# dual_encoder_shield_3v.net
KiCad netlist of a schematic drawn in EAGLE
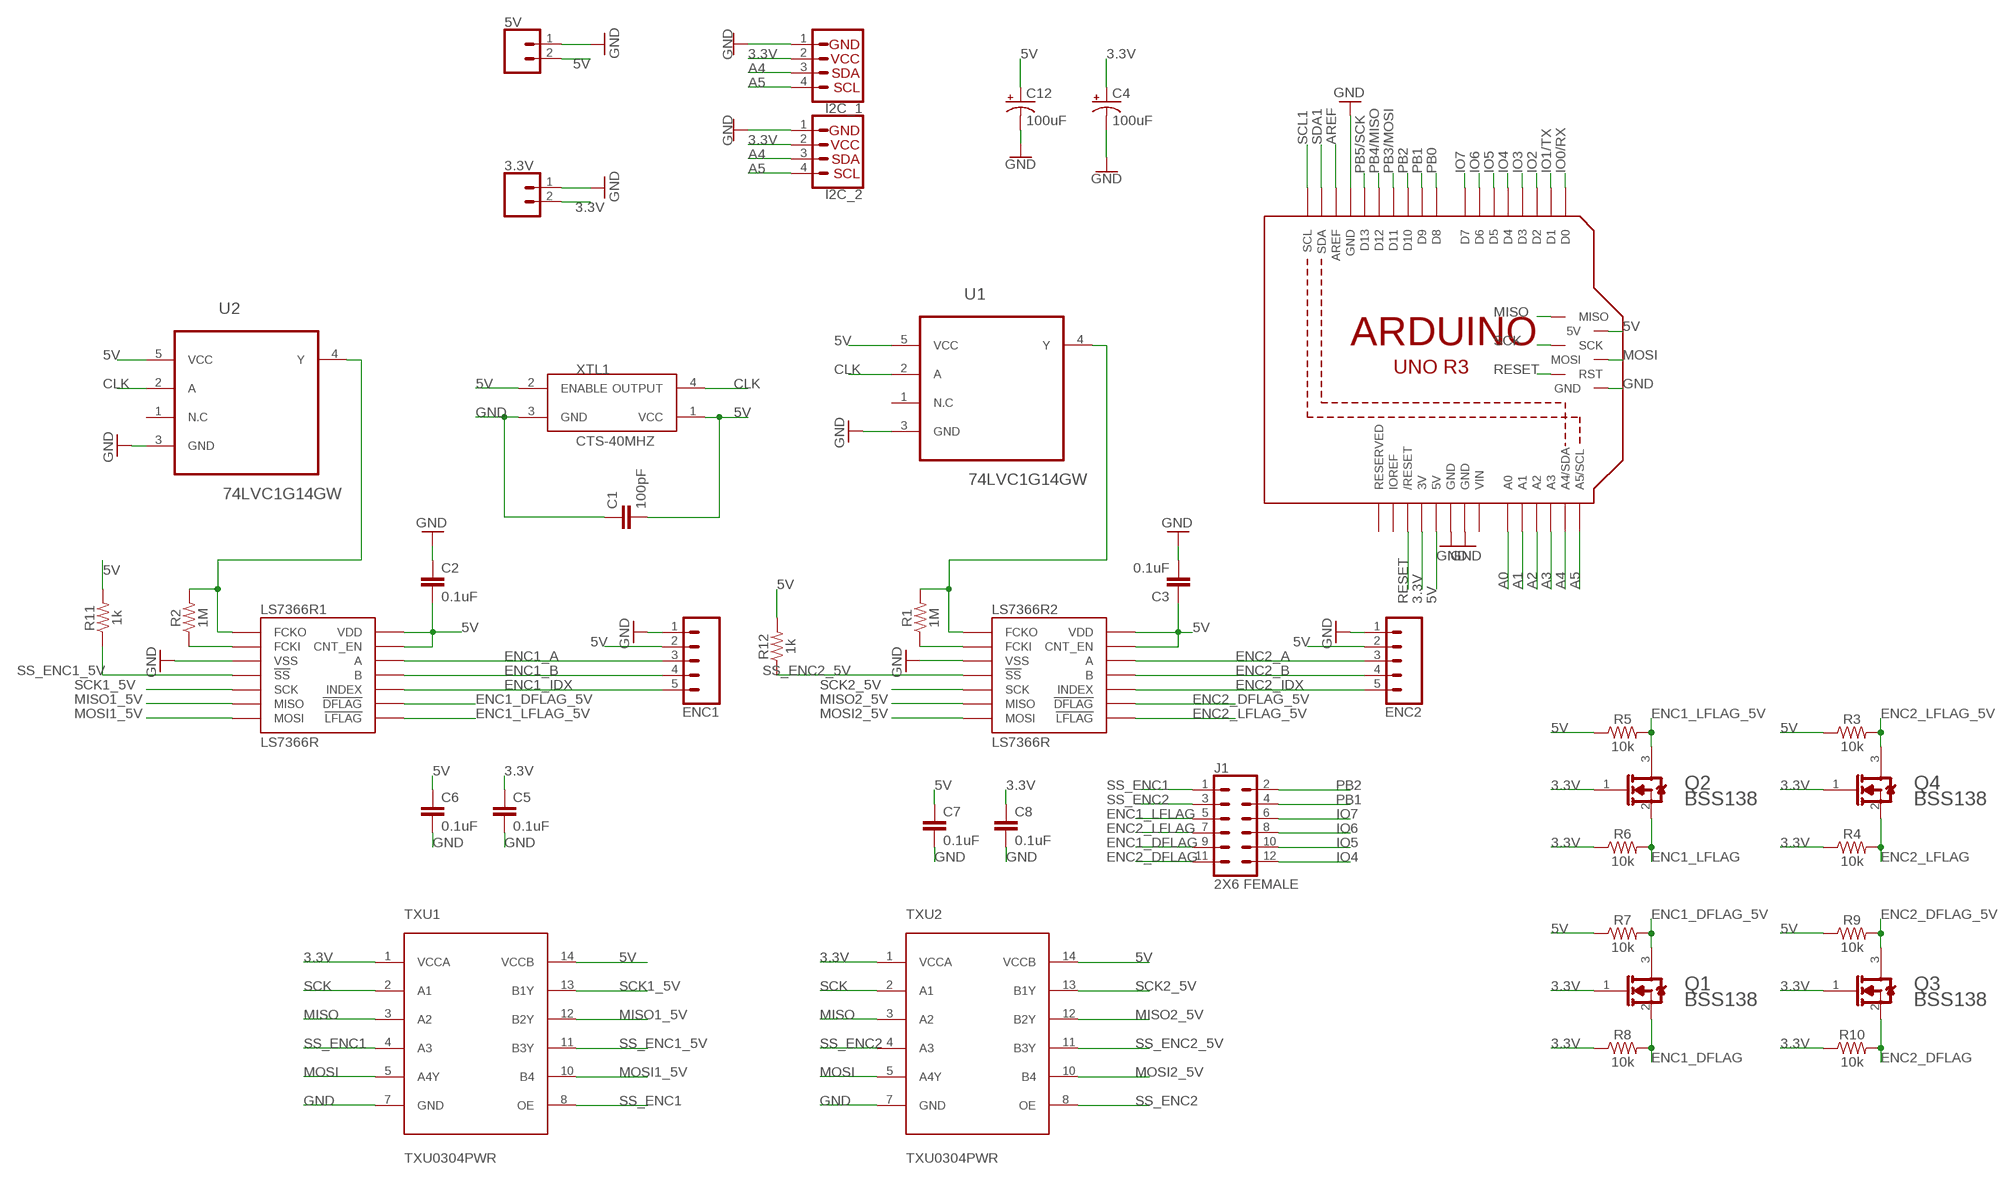
[diagram p0: schematic, sheet 1]

(export (version "E")
  (design (tool "Eeschema 10.0.6"))
  (components
    (comp (ref "3.3V")
      (value "CONN_02-JST-2MM-SMT")
      (footprint "eagle-import:JST-2-SMD")
      (libsource (lib "eagle-import") (part "CONN_02-JST-2MM-SMT"))
    )
    (comp (ref "5V")
      (value "CONN_02-JST-2MM-SMT")
      (footprint "eagle-import:JST-2-SMD")
      (libsource (lib "eagle-import") (part "CONN_02-JST-2MM-SMT"))
    )
    (comp (ref "C1")
      (value "100pF")
      (footprint "eagle-import:0603")
      (libsource (lib "eagle-import") (part "100PF-0603-50V-5%"))
    )
    (comp (ref "C2")
      (value "0.1uF")
      (footprint "eagle-import:0603")
      (libsource (lib "eagle-import") (part "0.1UF-0603-25V-5%"))
    )
    (comp (ref "C3")
      (value "0.1uF")
      (footprint "eagle-import:0603")
      (libsource (lib "eagle-import") (part "0.1UF-0603-25V-5%"))
    )
    (comp (ref "C4")
      (value "100uF")
      (footprint "eagle-import:PANASONIC_D")
      (libsource (lib "eagle-import") (part "100UF-POLAR-25V-20%(ELEC)"))
    )
    (comp (ref "C5")
      (value "0.1uF")
      (footprint "eagle-import:0603")
      (libsource (lib "eagle-import") (part "0.1UF-0603-25V-5%"))
    )
    (comp (ref "C6")
      (value "0.1uF")
      (footprint "eagle-import:0603")
      (libsource (lib "eagle-import") (part "0.1UF-0603-25V-5%"))
    )
    (comp (ref "C7")
      (value "0.1uF")
      (footprint "eagle-import:0603")
      (libsource (lib "eagle-import") (part "0.1UF-0603-25V-5%"))
    )
    (comp (ref "C8")
      (value "0.1uF")
      (footprint "eagle-import:0603")
      (libsource (lib "eagle-import") (part "0.1UF-0603-25V-5%"))
    )
    (comp (ref "C12")
      (value "100uF")
      (footprint "eagle-import:PANASONIC_D")
      (libsource (lib "eagle-import") (part "100UF-POLAR-25V-20%(ELEC)"))
    )
    (comp (ref "ENC1")
      (value "CONN_05")
      (footprint "eagle-import:1X05")
      (libsource (lib "eagle-import") (part "CONN_05"))
    )
    (comp (ref "ENC2")
      (value "CONN_05")
      (footprint "eagle-import:1X05")
      (libsource (lib "eagle-import") (part "CONN_05"))
    )
    (comp (ref "I2C_1")
      (value "QWIIC_CONNECTORJS-1MM")
      (footprint "eagle-import:JST04_1MM_RA")
      (libsource (lib "eagle-import") (part "QWIIC_CONNECTORJS-1MM"))
    )
    (comp (ref "I2C_2")
      (value "QWIIC_CONNECTORJS-1MM")
      (footprint "eagle-import:JST04_1MM_RA")
      (libsource (lib "eagle-import") (part "QWIIC_CONNECTORJS-1MM"))
    )
    (comp (ref "J1")
      (value "2X6 FEMALE")
      (footprint "eagle-import:2X6")
      (libsource (lib "eagle-import") (part "CONN_06X2PTH_FEMALE"))
    )
    (comp (ref "LS7366R1")
      (value "LS7366R")
      (footprint "eagle-import:SOIC14")
      (fields (field (name "MF") "LSI"))
      (libsource (lib "eagle-import") (part "LS7366R"))
    )
    (comp (ref "LS7366R2")
      (value "LS7366R")
      (footprint "eagle-import:SOIC14")
      (fields (field (name "MF") "LSI"))
      (libsource (lib "eagle-import") (part "LS7366R"))
    )
    (comp (ref "M1")
      (value "ARDUINO_R3_ICSP")
      (footprint "eagle-import:ARDUINOR3_ICSP")
      (libsource (lib "eagle-import") (part "ARDUINO_R3_ICSP"))
    )
    (comp (ref "Q1")
      (value "ON_SEMI_BSS138ON_SEMI_BSS138_0_0")
      (footprint "eagle-import:ON_SEMI_BSS138_0")
      (fields
        (field (name "DIGIKEY_PART_NUMBER") "BSS138CT-ND")
        (field (name "MF") "ON Semi")
        (field (name "MOUSER_PART_NUMBER") "512-BSS138")
      )
      (libsource (lib "eagle-import") (part "ON_SEMI_BSS138ON_SEMI_BSS138_0_0"))
    )
    (comp (ref "Q2")
      (value "ON_SEMI_BSS138ON_SEMI_BSS138_0_0")
      (footprint "eagle-import:ON_SEMI_BSS138_0")
      (fields
        (field (name "DIGIKEY_PART_NUMBER") "BSS138CT-ND")
        (field (name "MF") "ON Semi")
        (field (name "MOUSER_PART_NUMBER") "512-BSS138")
      )
      (libsource (lib "eagle-import") (part "ON_SEMI_BSS138ON_SEMI_BSS138_0_0"))
    )
    (comp (ref "Q3")
      (value "ON_SEMI_BSS138ON_SEMI_BSS138_0_0")
      (footprint "eagle-import:ON_SEMI_BSS138_0")
      (fields
        (field (name "DIGIKEY_PART_NUMBER") "BSS138CT-ND")
        (field (name "MF") "ON Semi")
        (field (name "MOUSER_PART_NUMBER") "512-BSS138")
      )
      (libsource (lib "eagle-import") (part "ON_SEMI_BSS138ON_SEMI_BSS138_0_0"))
    )
    (comp (ref "Q4")
      (value "ON_SEMI_BSS138ON_SEMI_BSS138_0_0")
      (footprint "eagle-import:ON_SEMI_BSS138_0")
      (fields
        (field (name "DIGIKEY_PART_NUMBER") "BSS138CT-ND")
        (field (name "MF") "ON Semi")
        (field (name "MOUSER_PART_NUMBER") "512-BSS138")
      )
      (libsource (lib "eagle-import") (part "ON_SEMI_BSS138ON_SEMI_BSS138_0_0"))
    )
    (comp (ref "R1")
      (value "1M")
      (footprint "eagle-import:0603")
      (libsource (lib "eagle-import") (part "1MOHM-0603-1/4W-5%"))
    )
    (comp (ref "R2")
      (value "1M")
      (footprint "eagle-import:0603")
      (libsource (lib "eagle-import") (part "1MOHM-0603-1/4W-5%"))
    )
    (comp (ref "R3")
      (value "10k")
      (footprint "eagle-import:0603")
      (libsource (lib "eagle-import") (part "10KOHM-0603-1/10W-1%"))
    )
    (comp (ref "R4")
      (value "10k")
      (footprint "eagle-import:0603")
      (libsource (lib "eagle-import") (part "10KOHM-0603-1/10W-1%"))
    )
    (comp (ref "R5")
      (value "10k")
      (footprint "eagle-import:0603")
      (libsource (lib "eagle-import") (part "10KOHM-0603-1/10W-1%"))
    )
    (comp (ref "R6")
      (value "10k")
      (footprint "eagle-import:0603")
      (libsource (lib "eagle-import") (part "10KOHM-0603-1/10W-1%"))
    )
    (comp (ref "R7")
      (value "10k")
      (footprint "eagle-import:0603")
      (libsource (lib "eagle-import") (part "10KOHM-0603-1/10W-1%"))
    )
    (comp (ref "R8")
      (value "10k")
      (footprint "eagle-import:0603")
      (libsource (lib "eagle-import") (part "10KOHM-0603-1/10W-1%"))
    )
    (comp (ref "R9")
      (value "10k")
      (footprint "eagle-import:0603")
      (libsource (lib "eagle-import") (part "10KOHM-0603-1/10W-1%"))
    )
    (comp (ref "R10")
      (value "10k")
      (footprint "eagle-import:0603")
      (libsource (lib "eagle-import") (part "10KOHM-0603-1/10W-1%"))
    )
    (comp (ref "R11")
      (value "1k")
      (footprint "eagle-import:0603")
      (libsource (lib "eagle-import") (part "1KOHM-0603-1/10W-1%"))
    )
    (comp (ref "R12")
      (value "1k")
      (footprint "eagle-import:0603")
      (libsource (lib "eagle-import") (part "1KOHM-0603-1/10W-1%"))
    )
    (comp (ref "TXU1")
      (value "TXU0304PWR")
      (footprint "eagle-import:SOP65P640X95-14N")
      (libsource (lib "eagle-import") (part "TXU0304PWR"))
    )
    (comp (ref "TXU2")
      (value "TXU0304PWR")
      (footprint "eagle-import:SOP65P640X95-14N")
      (libsource (lib "eagle-import") (part "TXU0304PWR"))
    )
    (comp (ref "U1")
      (value "74LVC1G14GW")
      (footprint "eagle-import:SOT65P210X110-5N")
      (fields (field (name "MF") "NXP Semiconductors"))
      (libsource (lib "eagle-import") (part "74LVC1G14GW"))
    )
    (comp (ref "U2")
      (value "74LVC1G14GW")
      (footprint "eagle-import:SOT65P210X110-5N")
      (fields (field (name "MF") "NXP Semiconductors"))
      (libsource (lib "eagle-import") (part "74LVC1G14GW"))
    )
    (comp (ref "XTL1")
      (value "CTS-40MHZ")
      (footprint "eagle-import:SOIC254P1016X440-4N")
      (libsource (lib "eagle-import") (part "CTS-40MHZ"))
    )
  )
  (nets
    (net (code "1") (name "/3.3V") (class "Default")
      (node (ref "3.3V") (pin "2") (pinfunction "1_2") (pintype "passive"))
      (node (ref "C4") (pin "+") (pinfunction "+_+") (pintype "passive"))
      (node (ref "C5") (pin "1") (pinfunction "1_1") (pintype "passive"))
      (node (ref "C8") (pin "1") (pinfunction "1_1") (pintype "passive"))
      (node (ref "I2C_1") (pin "2") (pinfunction "2_2") (pintype "power_in"))
      (node (ref "I2C_2") (pin "2") (pinfunction "2_2") (pintype "power_in"))
      (node (ref "M1") (pin "3V") (pinfunction "3V_3V") (pintype "power_in"))
      (node (ref "Q1") (pin "1") (pinfunction "G_1") (pintype "bidirectional"))
      (node (ref "Q2") (pin "1") (pinfunction "G_1") (pintype "bidirectional"))
      (node (ref "Q3") (pin "1") (pinfunction "G_1") (pintype "bidirectional"))
      (node (ref "Q4") (pin "1") (pinfunction "G_1") (pintype "bidirectional"))
      (node (ref "R10") (pin "1") (pinfunction "1_1") (pintype "passive"))
      (node (ref "R4") (pin "1") (pinfunction "1_1") (pintype "passive"))
      (node (ref "R6") (pin "1") (pinfunction "1_1") (pintype "passive"))
      (node (ref "R8") (pin "1") (pinfunction "1_1") (pintype "passive"))
      (node (ref "TXU1") (pin "1") (pinfunction "VCCA_1") (pintype "bidirectional"))
      (node (ref "TXU2") (pin "1") (pinfunction "VCCA_1") (pintype "bidirectional"))
    )
    (net (code "2") (name "/5V") (class "Default")
      (node (ref "5V") (pin "2") (pinfunction "1_2") (pintype "passive"))
      (node (ref "C1") (pin "2") (pinfunction "2_2") (pintype "passive"))
      (node (ref "C12") (pin "+") (pinfunction "+_+") (pintype "passive"))
      (node (ref "C2") (pin "2") (pinfunction "2_2") (pintype "passive"))
      (node (ref "C3") (pin "1") (pinfunction "1_1") (pintype "passive"))
      (node (ref "C6") (pin "1") (pinfunction "1_1") (pintype "passive"))
      (node (ref "C7") (pin "1") (pinfunction "1_1") (pintype "passive"))
      (node (ref "ENC1") (pin "2") (pinfunction "2_2") (pintype "passive"))
      (node (ref "ENC2") (pin "2") (pinfunction "2_2") (pintype "passive"))
      (node (ref "LS7366R1") (pin "13") (pinfunction "CNT_EN_13") (pintype "bidirectional"))
      (node (ref "LS7366R1") (pin "14") (pinfunction "VDD_14") (pintype "bidirectional"))
      (node (ref "LS7366R2") (pin "13") (pinfunction "CNT_EN_13") (pintype "bidirectional"))
      (node (ref "LS7366R2") (pin "14") (pinfunction "VDD_14") (pintype "bidirectional"))
      (node (ref "M1") (pin "5V") (pinfunction "5V_5V") (pintype "power_in"))
      (node (ref "M1") (pin "5V_ICSP") (pinfunction "5V_5V_ICSP") (pintype "passive"))
      (node (ref "R11") (pin "2") (pinfunction "2_2") (pintype "passive"))
      (node (ref "R12") (pin "2") (pinfunction "2_2") (pintype "passive"))
      (node (ref "R3") (pin "1") (pinfunction "1_1") (pintype "passive"))
      (node (ref "R5") (pin "1") (pinfunction "1_1") (pintype "passive"))
      (node (ref "R7") (pin "1") (pinfunction "1_1") (pintype "passive"))
      (node (ref "R9") (pin "1") (pinfunction "1_1") (pintype "passive"))
      (node (ref "TXU1") (pin "14") (pinfunction "VCCB_14") (pintype "bidirectional"))
      (node (ref "TXU2") (pin "14") (pinfunction "VCCB_14") (pintype "bidirectional"))
      (node (ref "U1") (pin "5") (pinfunction "VCC_5") (pintype "power_in"))
      (node (ref "U2") (pin "5") (pinfunction "VCC_5") (pintype "power_in"))
      (node (ref "XTL1") (pin "1") (pinfunction "VCC_1") (pintype "bidirectional"))
      (node (ref "XTL1") (pin "2") (pinfunction "ENABLE_2") (pintype "bidirectional"))
    )
    (net (code "3") (name "/A0") (class "Default")
      (node (ref "M1") (pin "A0") (pinfunction "A0_A0") (pintype "bidirectional"))
    )
    (net (code "4") (name "/A1") (class "Default")
      (node (ref "M1") (pin "A1") (pinfunction "A1_A1") (pintype "bidirectional"))
    )
    (net (code "5") (name "/A2") (class "Default")
      (node (ref "M1") (pin "A2") (pinfunction "A2_A2") (pintype "bidirectional"))
    )
    (net (code "6") (name "/A3") (class "Default")
      (node (ref "M1") (pin "A3") (pinfunction "A3_A3") (pintype "bidirectional"))
    )
    (net (code "7") (name "/A4") (class "Default")
      (node (ref "I2C_1") (pin "3") (pinfunction "3_3") (pintype "passive"))
      (node (ref "I2C_2") (pin "3") (pinfunction "3_3") (pintype "passive"))
      (node (ref "M1") (pin "A4") (pinfunction "A4/SDA_A4") (pintype "bidirectional"))
    )
    (net (code "8") (name "/A5") (class "Default")
      (node (ref "I2C_1") (pin "4") (pinfunction "4_4") (pintype "passive"))
      (node (ref "I2C_2") (pin "4") (pinfunction "4_4") (pintype "passive"))
      (node (ref "M1") (pin "A5") (pinfunction "A5/SCL_A5") (pintype "bidirectional"))
    )
    (net (code "9") (name "/AREF") (class "Default")
      (node (ref "M1") (pin "AREF") (pinfunction "AREF_AREF") (pintype "bidirectional"))
    )
    (net (code "10") (name "/CLK") (class "Default")
      (node (ref "U1") (pin "2") (pinfunction "A_2") (pintype "input"))
      (node (ref "U2") (pin "2") (pinfunction "A_2") (pintype "input"))
      (node (ref "XTL1") (pin "4") (pinfunction "OUTPUT_4") (pintype "bidirectional"))
    )
    (net (code "11") (name "/ENC1_A") (class "Default")
      (node (ref "ENC1") (pin "3") (pinfunction "3_3") (pintype "passive"))
      (node (ref "LS7366R1") (pin "12") (pinfunction "A_12") (pintype "bidirectional"))
    )
    (net (code "12") (name "/ENC1_B") (class "Default")
      (node (ref "ENC1") (pin "4") (pinfunction "4_4") (pintype "passive"))
      (node (ref "LS7366R1") (pin "11") (pinfunction "B_11") (pintype "bidirectional"))
    )
    (net (code "13") (name "/ENC1_DFLAG") (class "Default")
      (node (ref "J1") (pin "9") (pinfunction "9_9") (pintype "passive"))
      (node (ref "Q1") (pin "2") (pinfunction "S_2") (pintype "bidirectional"))
      (node (ref "R8") (pin "2") (pinfunction "2_2") (pintype "passive"))
    )
    (net (code "14") (name "/ENC1_DFLAG_5V") (class "Default")
      (node (ref "LS7366R1") (pin "9") (pinfunction "~{DFLAG}_9") (pintype "bidirectional"))
      (node (ref "Q1") (pin "3") (pinfunction "D_3") (pintype "bidirectional"))
      (node (ref "R7") (pin "2") (pinfunction "2_2") (pintype "passive"))
    )
    (net (code "15") (name "/ENC1_IDX") (class "Default")
      (node (ref "ENC1") (pin "5") (pinfunction "5_5") (pintype "passive"))
      (node (ref "LS7366R1") (pin "10") (pinfunction "INDEX_10") (pintype "bidirectional"))
    )
    (net (code "16") (name "/ENC1_LFLAG") (class "Default")
      (node (ref "J1") (pin "5") (pinfunction "5_5") (pintype "passive"))
      (node (ref "Q2") (pin "2") (pinfunction "S_2") (pintype "bidirectional"))
      (node (ref "R6") (pin "2") (pinfunction "2_2") (pintype "passive"))
    )
    (net (code "17") (name "/ENC1_LFLAG_5V") (class "Default")
      (node (ref "LS7366R1") (pin "8") (pinfunction "~{LFLAG}_8") (pintype "bidirectional"))
      (node (ref "Q2") (pin "3") (pinfunction "D_3") (pintype "bidirectional"))
      (node (ref "R5") (pin "2") (pinfunction "2_2") (pintype "passive"))
    )
    (net (code "18") (name "/ENC2_A") (class "Default")
      (node (ref "ENC2") (pin "3") (pinfunction "3_3") (pintype "passive"))
      (node (ref "LS7366R2") (pin "12") (pinfunction "A_12") (pintype "bidirectional"))
    )
    (net (code "19") (name "/ENC2_B") (class "Default")
      (node (ref "ENC2") (pin "4") (pinfunction "4_4") (pintype "passive"))
      (node (ref "LS7366R2") (pin "11") (pinfunction "B_11") (pintype "bidirectional"))
    )
    (net (code "20") (name "/ENC2_DFLAG") (class "Default")
      (node (ref "J1") (pin "11") (pinfunction "11_11") (pintype "passive"))
      (node (ref "Q3") (pin "2") (pinfunction "S_2") (pintype "bidirectional"))
      (node (ref "R10") (pin "2") (pinfunction "2_2") (pintype "passive"))
    )
    (net (code "21") (name "/ENC2_DFLAG_5V") (class "Default")
      (node (ref "LS7366R2") (pin "9") (pinfunction "~{DFLAG}_9") (pintype "bidirectional"))
      (node (ref "Q3") (pin "3") (pinfunction "D_3") (pintype "bidirectional"))
      (node (ref "R9") (pin "2") (pinfunction "2_2") (pintype "passive"))
    )
    (net (code "22") (name "/ENC2_IDX") (class "Default")
      (node (ref "ENC2") (pin "5") (pinfunction "5_5") (pintype "passive"))
      (node (ref "LS7366R2") (pin "10") (pinfunction "INDEX_10") (pintype "bidirectional"))
    )
    (net (code "23") (name "/ENC2_LFLAG") (class "Default")
      (node (ref "J1") (pin "7") (pinfunction "7_7") (pintype "passive"))
      (node (ref "Q4") (pin "2") (pinfunction "S_2") (pintype "bidirectional"))
      (node (ref "R4") (pin "2") (pinfunction "2_2") (pintype "passive"))
    )
    (net (code "24") (name "/ENC2_LFLAG_5V") (class "Default")
      (node (ref "LS7366R2") (pin "8") (pinfunction "~{LFLAG}_8") (pintype "bidirectional"))
      (node (ref "Q4") (pin "3") (pinfunction "D_3") (pintype "bidirectional"))
      (node (ref "R3") (pin "2") (pinfunction "2_2") (pintype "passive"))
    )
    (net (code "25") (name "/IO0{slash}RX") (class "Default")
      (node (ref "M1") (pin "D0") (pinfunction "D0_D0") (pintype "bidirectional"))
    )
    (net (code "26") (name "/IO1{slash}TX") (class "Default")
      (node (ref "M1") (pin "D1") (pinfunction "D1_D1") (pintype "bidirectional"))
    )
    (net (code "27") (name "/IO2") (class "Default")
      (node (ref "M1") (pin "D2") (pinfunction "D2_D2") (pintype "bidirectional"))
    )
    (net (code "28") (name "/IO3") (class "Default")
      (node (ref "M1") (pin "D3") (pinfunction "D3_D3") (pintype "bidirectional"))
    )
    (net (code "29") (name "/IO4") (class "Default")
      (node (ref "J1") (pin "12") (pinfunction "12_12") (pintype "passive"))
      (node (ref "M1") (pin "D4") (pinfunction "D4_D4") (pintype "bidirectional"))
    )
    (net (code "30") (name "/IO5") (class "Default")
      (node (ref "J1") (pin "10") (pinfunction "10_10") (pintype "passive"))
      (node (ref "M1") (pin "D5") (pinfunction "D5_D5") (pintype "bidirectional"))
    )
    (net (code "31") (name "/IO6") (class "Default")
      (node (ref "J1") (pin "8") (pinfunction "8_8") (pintype "passive"))
      (node (ref "M1") (pin "D6") (pinfunction "D6_D6") (pintype "bidirectional"))
    )
    (net (code "32") (name "/IO7") (class "Default")
      (node (ref "J1") (pin "6") (pinfunction "6_6") (pintype "passive"))
      (node (ref "M1") (pin "D7") (pinfunction "D7_D7") (pintype "bidirectional"))
    )
    (net (code "33") (name "/MISO") (class "Default")
      (node (ref "M1") (pin "MISO") (pinfunction "MISO_MISO") (pintype "passive"))
      (node (ref "TXU1") (pin "3") (pinfunction "A2_3") (pintype "bidirectional"))
      (node (ref "TXU2") (pin "3") (pinfunction "A2_3") (pintype "bidirectional"))
    )
    (net (code "34") (name "/MISO1_5V") (class "Default")
      (node (ref "LS7366R1") (pin "6") (pinfunction "MISO_6") (pintype "bidirectional"))
      (node (ref "TXU1") (pin "12") (pinfunction "B2Y_12") (pintype "bidirectional"))
    )
    (net (code "35") (name "/MISO2_5V") (class "Default")
      (node (ref "LS7366R2") (pin "6") (pinfunction "MISO_6") (pintype "bidirectional"))
      (node (ref "TXU2") (pin "12") (pinfunction "B2Y_12") (pintype "bidirectional"))
    )
    (net (code "36") (name "/MOSI") (class "Default")
      (node (ref "M1") (pin "MOSI") (pinfunction "MOSI_MOSI") (pintype "passive"))
      (node (ref "TXU1") (pin "5") (pinfunction "A4Y_5") (pintype "bidirectional"))
      (node (ref "TXU2") (pin "5") (pinfunction "A4Y_5") (pintype "bidirectional"))
    )
    (net (code "37") (name "/MOSI1_5V") (class "Default")
      (node (ref "LS7366R1") (pin "7") (pinfunction "MOSI_7") (pintype "bidirectional"))
      (node (ref "TXU1") (pin "10") (pinfunction "B4_10") (pintype "bidirectional"))
    )
    (net (code "38") (name "/MOSI2_5V") (class "Default")
      (node (ref "LS7366R2") (pin "7") (pinfunction "MOSI_7") (pintype "bidirectional"))
      (node (ref "TXU2") (pin "10") (pinfunction "B4_10") (pintype "bidirectional"))
    )
    (net (code "39") (name "/PB0") (class "Default")
      (node (ref "M1") (pin "D8") (pinfunction "D8_D8") (pintype "bidirectional"))
    )
    (net (code "40") (name "/PB1") (class "Default")
      (node (ref "J1") (pin "4") (pinfunction "4_4") (pintype "passive"))
      (node (ref "M1") (pin "D9") (pinfunction "D9_D9") (pintype "bidirectional"))
    )
    (net (code "41") (name "/PB2") (class "Default")
      (node (ref "J1") (pin "2") (pinfunction "2_2") (pintype "passive"))
      (node (ref "M1") (pin "D10") (pinfunction "D10_D10") (pintype "bidirectional"))
    )
    (net (code "42") (name "/PB3{slash}MOSI") (class "Default")
      (node (ref "M1") (pin "D11") (pinfunction "D11_D11") (pintype "bidirectional"))
    )
    (net (code "43") (name "/PB4{slash}MISO") (class "Default")
      (node (ref "M1") (pin "D12") (pinfunction "D12_D12") (pintype "bidirectional"))
    )
    (net (code "44") (name "/PB5{slash}SCK") (class "Default")
      (node (ref "M1") (pin "D13") (pinfunction "D13_D13") (pintype "bidirectional"))
    )
    (net (code "45") (name "/RESET") (class "Default")
      (node (ref "M1") (pin "RESET") (pinfunction "/RESET_RESET") (pintype "bidirectional"))
      (node (ref "M1") (pin "RESET_ICSP") (pinfunction "RST_RESET_ICSP") (pintype "passive"))
    )
    (net (code "46") (name "/SCK") (class "Default")
      (node (ref "M1") (pin "SCK") (pinfunction "SCK_SCK") (pintype "passive"))
      (node (ref "TXU1") (pin "2") (pinfunction "A1_2") (pintype "bidirectional"))
      (node (ref "TXU2") (pin "2") (pinfunction "A1_2") (pintype "bidirectional"))
    )
    (net (code "47") (name "/SCK1_5V") (class "Default")
      (node (ref "LS7366R1") (pin "5") (pinfunction "SCK_5") (pintype "bidirectional"))
      (node (ref "TXU1") (pin "13") (pinfunction "B1Y_13") (pintype "bidirectional"))
    )
    (net (code "48") (name "/SCK2_5V") (class "Default")
      (node (ref "LS7366R2") (pin "5") (pinfunction "SCK_5") (pintype "bidirectional"))
      (node (ref "TXU2") (pin "13") (pinfunction "B1Y_13") (pintype "bidirectional"))
    )
    (net (code "49") (name "/SCL1") (class "Default")
      (node (ref "M1") (pin "SCL") (pinfunction "SCL_SCL") (pintype "bidirectional"))
    )
    (net (code "50") (name "/SDA1") (class "Default")
      (node (ref "M1") (pin "SDA") (pinfunction "SDA_SDA") (pintype "bidirectional"))
    )
    (net (code "51") (name "/SS_ENC1") (class "Default")
      (node (ref "J1") (pin "1") (pinfunction "1_1") (pintype "passive"))
      (node (ref "TXU1") (pin "4") (pinfunction "A3_4") (pintype "bidirectional"))
      (node (ref "TXU1") (pin "8") (pinfunction "OE_8") (pintype "bidirectional"))
    )
    (net (code "52") (name "/SS_ENC1_5V") (class "Default")
      (node (ref "LS7366R1") (pin "4") (pinfunction "~{SS}_4") (pintype "bidirectional"))
      (node (ref "R11") (pin "1") (pinfunction "1_1") (pintype "passive"))
      (node (ref "TXU1") (pin "11") (pinfunction "B3Y_11") (pintype "bidirectional"))
    )
    (net (code "53") (name "/SS_ENC2") (class "Default")
      (node (ref "J1") (pin "3") (pinfunction "3_3") (pintype "passive"))
      (node (ref "TXU2") (pin "4") (pinfunction "A3_4") (pintype "bidirectional"))
      (node (ref "TXU2") (pin "8") (pinfunction "OE_8") (pintype "bidirectional"))
    )
    (net (code "54") (name "/SS_ENC2_5V") (class "Default")
      (node (ref "LS7366R2") (pin "4") (pinfunction "~{SS}_4") (pintype "bidirectional"))
      (node (ref "R12") (pin "1") (pinfunction "1_1") (pintype "passive"))
      (node (ref "TXU2") (pin "11") (pinfunction "B3Y_11") (pintype "bidirectional"))
    )
    (net (code "55") (name "/VIN") (class "Default")
      (node (ref "M1") (pin "VIN") (pinfunction "VIN_VIN") (pintype "power_in"))
    )
    (net (code "56") (name "GND") (class "Default")
      (node (ref "3.3V") (pin "1") (pinfunction "2_1") (pintype "passive"))
      (node (ref "5V") (pin "1") (pinfunction "2_1") (pintype "passive"))
      (node (ref "C1") (pin "1") (pinfunction "1_1") (pintype "passive"))
      (node (ref "C12") (pin "-") (pinfunction "-_-") (pintype "passive"))
      (node (ref "C2") (pin "1") (pinfunction "1_1") (pintype "passive"))
      (node (ref "C3") (pin "2") (pinfunction "2_2") (pintype "passive"))
      (node (ref "C4") (pin "-") (pinfunction "-_-") (pintype "passive"))
      (node (ref "C5") (pin "2") (pinfunction "2_2") (pintype "passive"))
      (node (ref "C6") (pin "2") (pinfunction "2_2") (pintype "passive"))
      (node (ref "C7") (pin "2") (pinfunction "2_2") (pintype "passive"))
      (node (ref "C8") (pin "2") (pinfunction "2_2") (pintype "passive"))
      (node (ref "ENC1") (pin "1") (pinfunction "1_1") (pintype "passive"))
      (node (ref "ENC2") (pin "1") (pinfunction "1_1") (pintype "passive"))
      (node (ref "I2C_1") (pin "1") (pinfunction "1_1") (pintype "power_in"))
      (node (ref "I2C_2") (pin "1") (pinfunction "1_1") (pintype "power_in"))
      (node (ref "LS7366R1") (pin "3") (pinfunction "VSS_3") (pintype "bidirectional"))
      (node (ref "LS7366R2") (pin "3") (pinfunction "VSS_3") (pintype "bidirectional"))
      (node (ref "M1") (pin "GND") (pinfunction "GND_GND") (pintype "power_in"))
      (node (ref "M1") (pin "GND@1") (pinfunction "GND_GND@1") (pintype "power_in"))
      (node (ref "M1") (pin "GND@2") (pinfunction "GND_GND@2") (pintype "passive"))
      (node (ref "M1") (pin "GND@3") (pinfunction "GND_GND@3") (pintype "power_in"))
      (node (ref "TXU1") (pin "7") (pinfunction "GND_7") (pintype "bidirectional"))
      (node (ref "TXU2") (pin "7") (pinfunction "GND_7") (pintype "bidirectional"))
      (node (ref "U1") (pin "3") (pinfunction "GND_3") (pintype "passive"))
      (node (ref "U2") (pin "3") (pinfunction "GND_3") (pintype "passive"))
      (node (ref "XTL1") (pin "3") (pinfunction "GND_3") (pintype "bidirectional"))
    )
    (net (code "57") (name "Net-(LS7366R1-FCKI)") (class "Default")
      (node (ref "LS7366R1") (pin "2") (pinfunction "FCKI_2") (pintype "bidirectional"))
      (node (ref "R2") (pin "1") (pinfunction "1_1") (pintype "passive"))
    )
    (net (code "58") (name "Net-(LS7366R1-FCKO)") (class "Default")
      (node (ref "LS7366R1") (pin "1") (pinfunction "FCKO_1") (pintype "bidirectional"))
      (node (ref "R2") (pin "2") (pinfunction "2_2") (pintype "passive"))
      (node (ref "U2") (pin "4") (pinfunction "Y_4") (pintype "output"))
    )
    (net (code "59") (name "Net-(LS7366R2-FCKI)") (class "Default")
      (node (ref "LS7366R2") (pin "2") (pinfunction "FCKI_2") (pintype "bidirectional"))
      (node (ref "R1") (pin "1") (pinfunction "1_1") (pintype "passive"))
    )
    (net (code "60") (name "Net-(LS7366R2-FCKO)") (class "Default")
      (node (ref "LS7366R2") (pin "1") (pinfunction "FCKO_1") (pintype "bidirectional"))
      (node (ref "R1") (pin "2") (pinfunction "2_2") (pintype "passive"))
      (node (ref "U1") (pin "4") (pinfunction "Y_4") (pintype "output"))
    )
    (net (code "61") (name "unconnected-(M1-PadIOREF)") (class "Default")
      (node (ref "M1") (pin "IOREF") (pinfunction "IOREF_IOREF") (pintype "output"))
    )
    (net (code "62") (name "unconnected-(M1-PadRESERVED)") (class "Default")
      (node (ref "M1") (pin "RESERVED") (pinfunction "RESERVED_RESERVED") (pintype "no_connect"))
    )
    (net (code "63") (name "unconnected-(U1-N.C-Pad1)") (class "Default")
      (node (ref "U1") (pin "1") (pinfunction "N.C_1") (pintype "no_connect"))
    )
    (net (code "64") (name "unconnected-(U2-N.C-Pad1)") (class "Default")
      (node (ref "U2") (pin "1") (pinfunction "N.C_1") (pintype "no_connect"))
    )
  )
)
